# Servo_driver.net
KiCad netlist of a schematic drawn in Altium Designer
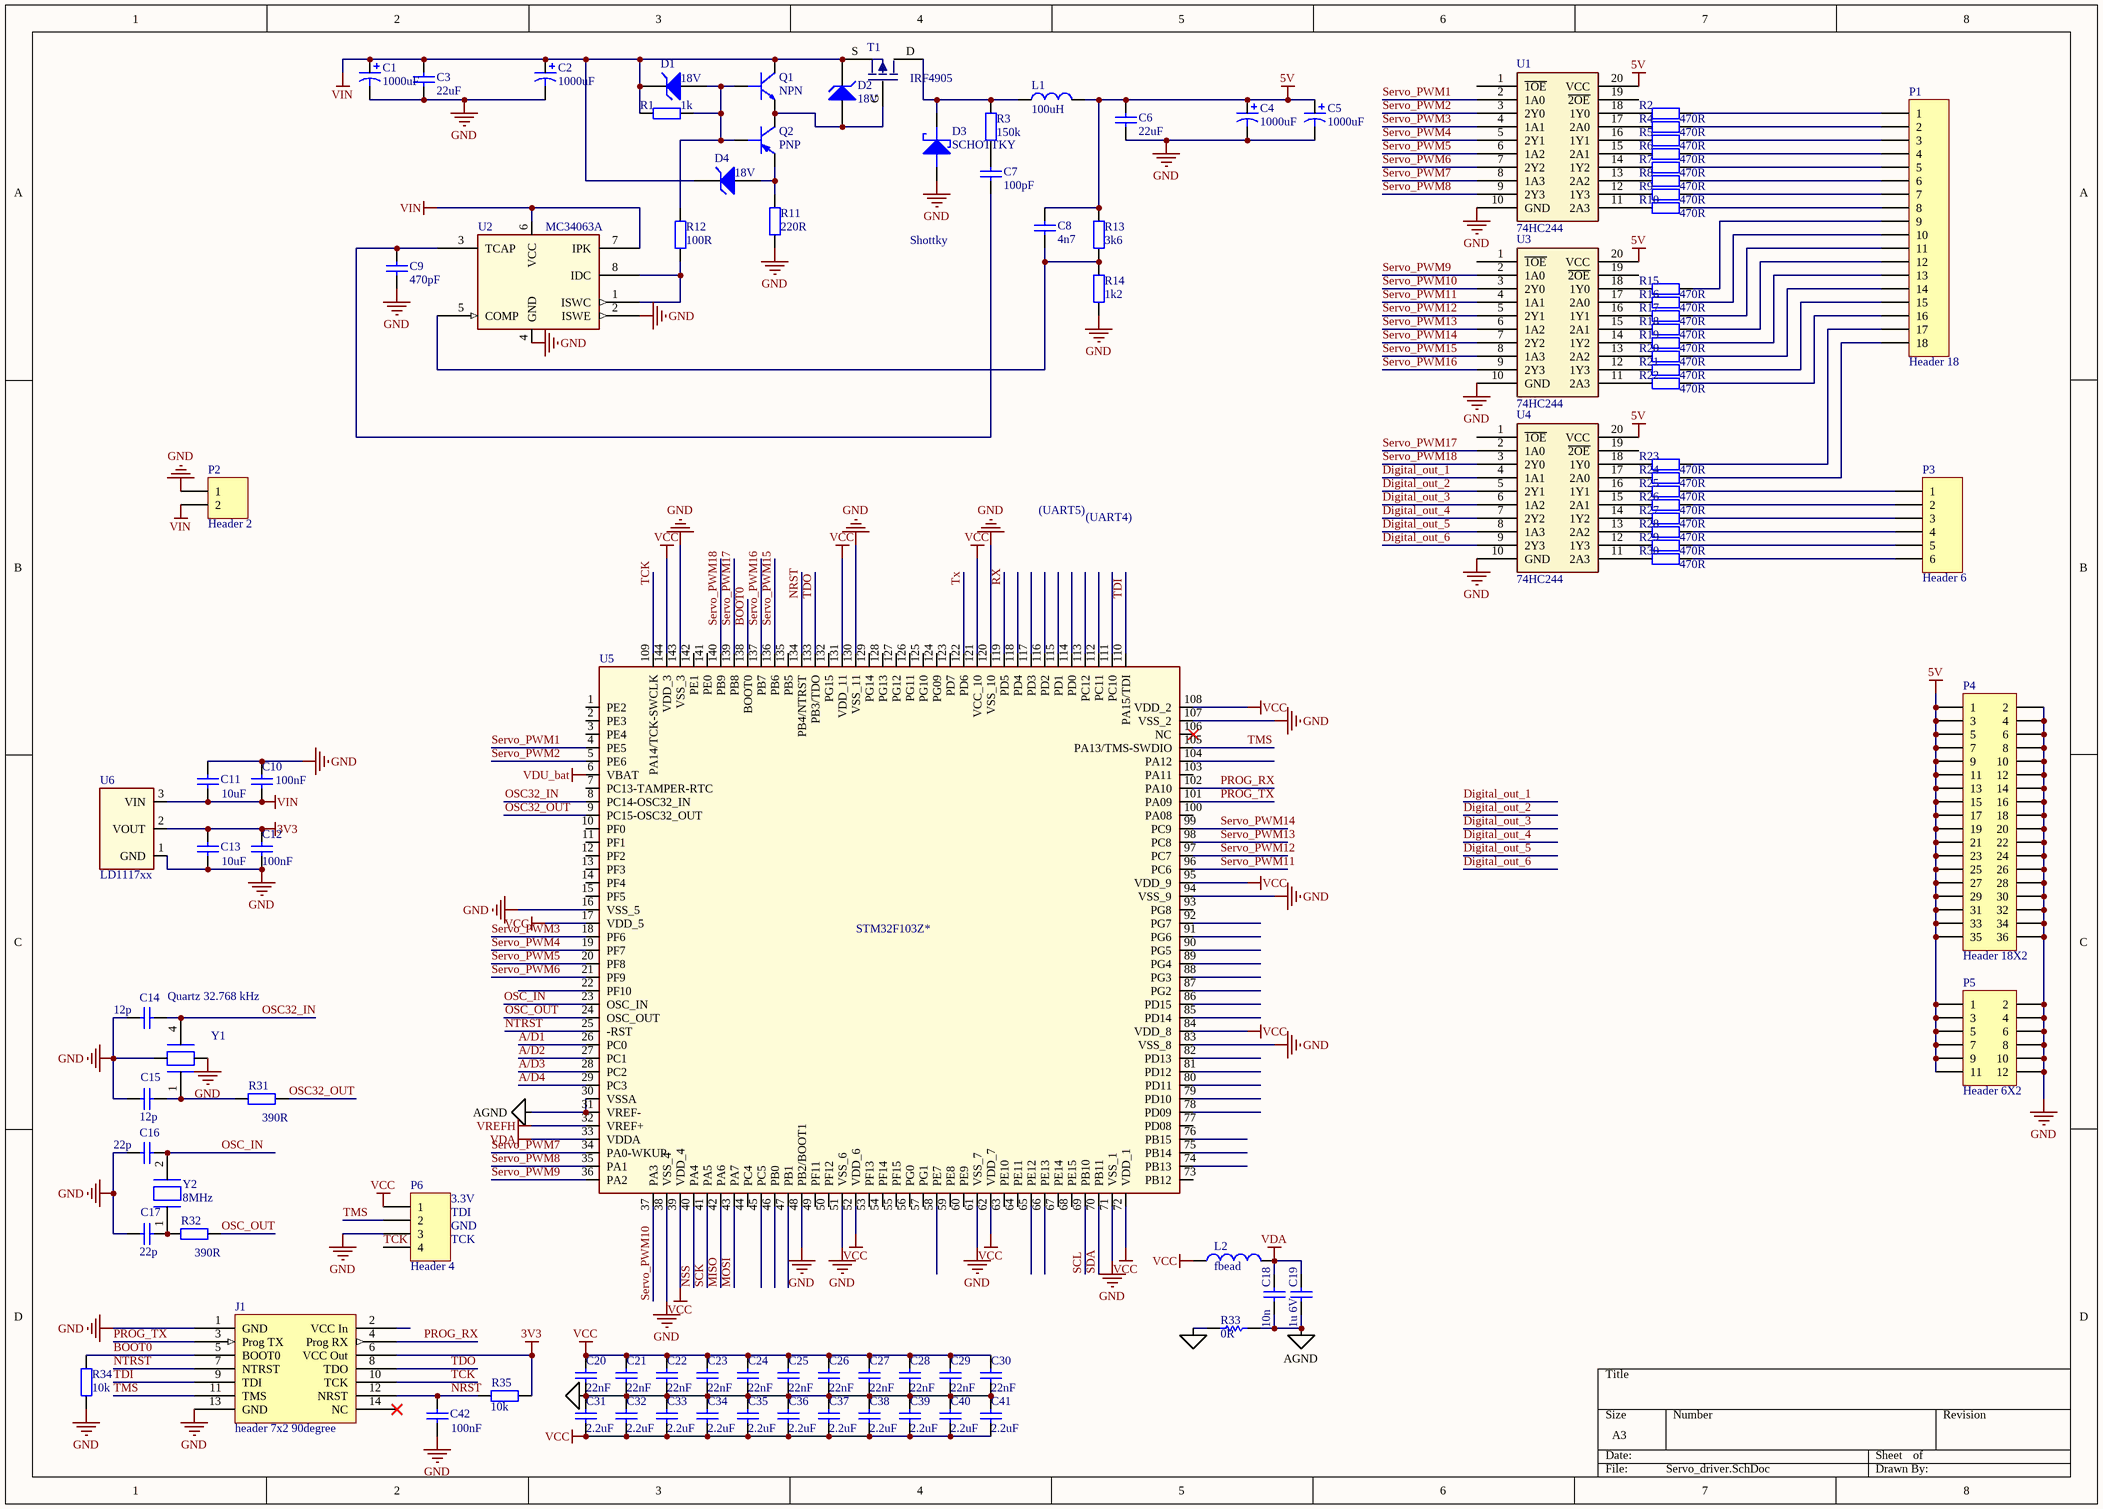
[diagram p0: Servo_driver.SchDoc]

(export (version "E")
  (design (tool "Eeschema 10.0.6"))
  (components
    (comp (ref "C1")
      (value "1000uF")
      (footprint "cap_10x12")
      (description "Polarized Capacitor")
      (libsource (lib "Capacitor") (part "CAP_ELECT"))
    )
    (comp (ref "C2")
      (value "1000uF")
      (footprint "cap_10x12")
      (description "Polarized Capacitor")
      (libsource (lib "Capacitor") (part "CAP_ELECT"))
    )
    (comp (ref "C3")
      (value "22uF")
      (footprint "FP_1210_CAP_N")
      (description "Capacitor")
      (libsource (lib "Capacitor") (part "CAP"))
    )
    (comp (ref "C4")
      (value "1000uF")
      (footprint "cap_10x12")
      (description "Polarized Capacitor")
      (libsource (lib "Capacitor") (part "CAP_ELECT"))
    )
    (comp (ref "C5")
      (value "1000uF")
      (footprint "cap_10x12")
      (description "Polarized Capacitor")
      (libsource (lib "Capacitor") (part "CAP_ELECT"))
    )
    (comp (ref "C6")
      (value "22uF")
      (footprint "FP_1210_CAP_N")
      (description "Capacitor")
      (libsource (lib "Capacitor") (part "CAP"))
    )
    (comp (ref "C7")
      (value "100pF")
      (footprint "FP_0603_CAP_080")
      (description "Capacitor")
      (fields (field (name "PUBLISHER") "Altium Limited"))
      (libsource (lib "Miscellaneous Devices") (part "Cap"))
    )
    (comp (ref "C8")
      (value "4n7")
      (footprint "FP_0603_CAP_080")
      (description "Capacitor")
      (fields (field (name "PUBLISHER") "Altium Limited"))
      (libsource (lib "Miscellaneous Devices") (part "Cap"))
    )
    (comp (ref "C9")
      (value "470pF")
      (footprint "FP_0603_CAP_080")
      (description "Capacitor")
      (fields (field (name "PUBLISHER") "Altium Limited"))
      (libsource (lib "Miscellaneous Devices") (part "Cap"))
    )
    (comp (ref "C10")
      (value "100nF")
      (footprint "FP_0603_CAP_080")
      (description "Capacitor")
      (fields (field (name "PUBLISHER") "Altium Limited"))
      (libsource (lib "Miscellaneous Devices") (part "Cap"))
    )
    (comp (ref "C11")
      (value "10uF")
      (footprint "FP_1206_CAP_085")
      (description "Capacitor")
      (fields (field (name "PUBLISHER") "Altium Limited"))
      (libsource (lib "Miscellaneous Devices") (part "Cap"))
    )
    (comp (ref "C12")
      (value "100nF")
      (footprint "FP_0603_CAP_080")
      (description "Capacitor")
      (fields (field (name "PUBLISHER") "Altium Limited"))
      (libsource (lib "Miscellaneous Devices") (part "Cap"))
    )
    (comp (ref "C13")
      (value "10uF")
      (footprint "FP_1206_CAP_085")
      (description "Capacitor")
      (fields (field (name "PUBLISHER") "Altium Limited"))
      (libsource (lib "Miscellaneous Devices") (part "Cap"))
    )
    (comp (ref "C14")
      (value "12p")
      (footprint "FP_0603_CAP_080")
      (description "Capacitor")
      (fields (field (name "PUBLISHER") "Altium Limited"))
      (libsource (lib "Miscellaneous Devices") (part "Cap"))
    )
    (comp (ref "C15")
      (value "12p")
      (footprint "FP_0603_CAP_080")
      (description "Capacitor")
      (fields (field (name "PUBLISHER") "Altium Limited"))
      (libsource (lib "Miscellaneous Devices") (part "Cap"))
    )
    (comp (ref "C16")
      (value "22p")
      (footprint "FP_0603_CAP_080")
      (description "Capacitor")
      (fields (field (name "PUBLISHER") "Altium Limited"))
      (libsource (lib "Miscellaneous Devices") (part "Cap"))
    )
    (comp (ref "C17")
      (value "22p")
      (footprint "FP_0603_CAP_080")
      (description "Capacitor")
      (fields (field (name "PUBLISHER") "Altium Limited"))
      (libsource (lib "Miscellaneous Devices") (part "Cap"))
    )
    (comp (ref "C18")
      (value "10n")
      (footprint "FP_0603_CAP_080")
      (description "Capacitor")
      (fields (field (name "PUBLISHER") "Altium Limited"))
      (libsource (lib "Miscellaneous Devices") (part "Cap"))
    )
    (comp (ref "C19")
      (value "1u 6V")
      (footprint "FP_0603_CAP_080")
      (description "Capacitor")
      (fields (field (name "PUBLISHER") "Altium Limited"))
      (libsource (lib "Miscellaneous Devices") (part "Cap"))
    )
    (comp (ref "C20")
      (value "22nF")
      (footprint "FP_0603_CAP_080")
      (description "Capacitor")
      (fields (field (name "PUBLISHER") "Altium Limited"))
      (libsource (lib "Miscellaneous Devices") (part "Cap"))
    )
    (comp (ref "C21")
      (value "22nF")
      (footprint "FP_0603_CAP_080")
      (description "Capacitor")
      (fields (field (name "PUBLISHER") "Altium Limited"))
      (libsource (lib "Miscellaneous Devices") (part "Cap"))
    )
    (comp (ref "C22")
      (value "22nF")
      (footprint "FP_0603_CAP_080")
      (description "Capacitor")
      (fields (field (name "PUBLISHER") "Altium Limited"))
      (libsource (lib "Miscellaneous Devices") (part "Cap"))
    )
    (comp (ref "C23")
      (value "22nF")
      (footprint "FP_0603_CAP_080")
      (description "Capacitor")
      (fields (field (name "PUBLISHER") "Altium Limited"))
      (libsource (lib "Miscellaneous Devices") (part "Cap"))
    )
    (comp (ref "C24")
      (value "22nF")
      (footprint "FP_0603_CAP_080")
      (description "Capacitor")
      (fields (field (name "PUBLISHER") "Altium Limited"))
      (libsource (lib "Miscellaneous Devices") (part "Cap"))
    )
    (comp (ref "C25")
      (value "22nF")
      (footprint "FP_0603_CAP_080")
      (description "Capacitor")
      (fields (field (name "PUBLISHER") "Altium Limited"))
      (libsource (lib "Miscellaneous Devices") (part "Cap"))
    )
    (comp (ref "C26")
      (value "22nF")
      (footprint "FP_0603_CAP_080")
      (description "Capacitor")
      (fields (field (name "PUBLISHER") "Altium Limited"))
      (libsource (lib "Miscellaneous Devices") (part "Cap"))
    )
    (comp (ref "C27")
      (value "22nF")
      (footprint "FP_0603_CAP_080")
      (description "Capacitor")
      (fields (field (name "PUBLISHER") "Altium Limited"))
      (libsource (lib "Miscellaneous Devices") (part "Cap"))
    )
    (comp (ref "C28")
      (value "22nF")
      (footprint "FP_0603_CAP_080")
      (description "Capacitor")
      (fields (field (name "PUBLISHER") "Altium Limited"))
      (libsource (lib "Miscellaneous Devices") (part "Cap"))
    )
    (comp (ref "C29")
      (value "22nF")
      (footprint "FP_0603_CAP_080")
      (description "Capacitor")
      (fields (field (name "PUBLISHER") "Altium Limited"))
      (libsource (lib "Miscellaneous Devices") (part "Cap"))
    )
    (comp (ref "C30")
      (value "22nF")
      (footprint "FP_0603_CAP_080")
      (description "Capacitor")
      (fields (field (name "PUBLISHER") "Altium Limited"))
      (libsource (lib "Miscellaneous Devices") (part "Cap"))
    )
    (comp (ref "C31")
      (value "2.2uF")
      (footprint "FP_0603_CAP_080")
      (description "Capacitor")
      (fields (field (name "PUBLISHER") "Altium Limited"))
      (libsource (lib "Miscellaneous Devices") (part "Cap"))
    )
    (comp (ref "C32")
      (value "2.2uF")
      (footprint "FP_0603_CAP_080")
      (description "Capacitor")
      (fields (field (name "PUBLISHER") "Altium Limited"))
      (libsource (lib "Miscellaneous Devices") (part "Cap"))
    )
    (comp (ref "C33")
      (value "2.2uF")
      (footprint "FP_0603_CAP_080")
      (description "Capacitor")
      (fields (field (name "PUBLISHER") "Altium Limited"))
      (libsource (lib "Miscellaneous Devices") (part "Cap"))
    )
    (comp (ref "C34")
      (value "2.2uF")
      (footprint "FP_0603_CAP_080")
      (description "Capacitor")
      (fields (field (name "PUBLISHER") "Altium Limited"))
      (libsource (lib "Miscellaneous Devices") (part "Cap"))
    )
    (comp (ref "C35")
      (value "2.2uF")
      (footprint "FP_0603_CAP_080")
      (description "Capacitor")
      (fields (field (name "PUBLISHER") "Altium Limited"))
      (libsource (lib "Miscellaneous Devices") (part "Cap"))
    )
    (comp (ref "C36")
      (value "2.2uF")
      (footprint "FP_0603_CAP_080")
      (description "Capacitor")
      (fields (field (name "PUBLISHER") "Altium Limited"))
      (libsource (lib "Miscellaneous Devices") (part "Cap"))
    )
    (comp (ref "C37")
      (value "2.2uF")
      (footprint "FP_0603_CAP_080")
      (description "Capacitor")
      (fields (field (name "PUBLISHER") "Altium Limited"))
      (libsource (lib "Miscellaneous Devices") (part "Cap"))
    )
    (comp (ref "C38")
      (value "2.2uF")
      (footprint "FP_0603_CAP_080")
      (description "Capacitor")
      (fields (field (name "PUBLISHER") "Altium Limited"))
      (libsource (lib "Miscellaneous Devices") (part "Cap"))
    )
    (comp (ref "C39")
      (value "2.2uF")
      (footprint "FP_0603_CAP_080")
      (description "Capacitor")
      (fields (field (name "PUBLISHER") "Altium Limited"))
      (libsource (lib "Miscellaneous Devices") (part "Cap"))
    )
    (comp (ref "C40")
      (value "2.2uF")
      (footprint "FP_0603_CAP_080")
      (description "Capacitor")
      (fields (field (name "PUBLISHER") "Altium Limited"))
      (libsource (lib "Miscellaneous Devices") (part "Cap"))
    )
    (comp (ref "C41")
      (value "2.2uF")
      (footprint "FP_0603_CAP_080")
      (description "Capacitor")
      (fields (field (name "PUBLISHER") "Altium Limited"))
      (libsource (lib "Miscellaneous Devices") (part "Cap"))
    )
    (comp (ref "C42")
      (value "100nF")
      (footprint "FP_0603_CAP_080")
      (description "Capacitor")
      (fields (field (name "PUBLISHER") "Altium Limited"))
      (libsource (lib "Miscellaneous Devices") (part "Cap"))
    )
    (comp (ref "D1")
      (value "18V")
      (footprint "SOD-80")
      (description "Zener Diode")
      (libsource (lib "Diode") (part "ZENER"))
    )
    (comp (ref "D2")
      (value "18V")
      (footprint "SOD-80")
      (description "Zener Diode")
      (libsource (lib "Diode") (part "ZENER"))
    )
    (comp (ref "D3")
      (value "SCHOTTKY")
      (footprint "DIODE_TO220")
      (description "NXP - PMEG3020EJ,115 - SCHOTTKY RECT 30V 2A SOD323F")
      (libsource (lib "Diode") (part "SCHOTTKY"))
    )
    (comp (ref "D4")
      (value "18V")
      (footprint "SOD-80")
      (description "Zener Diode")
      (libsource (lib "Diode") (part "ZENER"))
    )
    (comp (ref "J1")
      (value "header 7x2 90degree")
      (footprint "SMD_header_2x7_narrow")
      (libsource (lib "Fufi_altium_lib") (part "ARM_JTAG_PROG"))
    )
    (comp (ref "L1") (value "100uH") (footprint "SRR1206_T") (libsource (lib "Inductor") (part "L")))
    (comp (ref "L2")
      (value "fbead")
      (footprint "FP_0805_RES_SIMPLE")
      (description "FBEAD")
      (fields (field (name "PUBLISHER") "Altium Limited"))
      (libsource (lib "Miscellaneous Devices") (part "Inductor"))
    )
    (comp (ref "P1")
      (value "Header 18")
      (footprint "HDR1X18")
      (description "Header, 18-Pin")
      (fields (field (name "PUBLISHER") "Altium Limited"))
      (libsource (lib "Miscellaneous Connectors") (part "Header 18"))
    )
    (comp (ref "P2")
      (value "Header 2")
      (footprint "Sorkapocs 2P 5mm")
      (description "Header, 2-Pin")
      (fields (field (name "PUBLISHER") "Altium Limited"))
      (libsource (lib "Miscellaneous Connectors") (part "Header 2"))
    )
    (comp (ref "P3")
      (value "Header 6")
      (footprint "HDR1X6")
      (description "Header, 6-Pin")
      (fields (field (name "PUBLISHER") "Altium Limited"))
      (libsource (lib "Miscellaneous Connectors") (part "Header 6"))
    )
    (comp (ref "P4")
      (value "Header 18X2")
      (footprint "HDR2X18")
      (description "Header, 18-Pin, Dual row")
      (fields (field (name "PUBLISHER") "Altium Limited"))
      (libsource (lib "Miscellaneous Connectors") (part "Header 18X2"))
    )
    (comp (ref "P5")
      (value "Header 6X2")
      (footprint "HDR2X6")
      (description "Header, 6-Pin, Dual row")
      (fields (field (name "PUBLISHER") "Altium Limited"))
      (libsource (lib "Miscellaneous Connectors") (part "Header 6X2"))
    )
    (comp (ref "P6")
      (value "Header 4")
      (footprint "HDR1X4")
      (description "Header, 4-Pin")
      (fields (field (name "PUBLISHER") "Altium Limited"))
      (libsource (lib "Miscellaneous Connectors") (part "Header 4"))
    )
    (comp (ref "Q1") (value "NPN") (footprint "TR_SOT23") (libsource (lib "Transistor") (part "NPN")))
    (comp (ref "Q2") (value "PNP") (footprint "TR_SOT23") (libsource (lib "Transistor") (part "PNP")))
    (comp (ref "R1")
      (value "1k")
      (footprint "FP_1206_RES")
      (description "Resistor")
      (fields (field (name "PUBLISHER") "Altium Limited"))
      (libsource (lib "") (part "Res3_1"))
    )
    (comp (ref "R2")
      (value "470R")
      (footprint "FP_0603_RES")
      (description "Resistor")
      (fields (field (name "PUBLISHER") "Altium Limited"))
      (libsource (lib "Miscellaneous Devices") (part "Res3"))
    )
    (comp (ref "R3")
      (value "150k")
      (footprint "FP_0603_RES")
      (description "Resistor")
      (fields (field (name "PUBLISHER") "Altium Limited"))
      (libsource (lib "") (part "Res3_3"))
    )
    (comp (ref "R4")
      (value "470R")
      (footprint "FP_0603_RES")
      (description "Resistor")
      (fields (field (name "PUBLISHER") "Altium Limited"))
      (libsource (lib "Miscellaneous Devices") (part "Res3"))
    )
    (comp (ref "R5")
      (value "470R")
      (footprint "FP_0603_RES")
      (description "Resistor")
      (fields (field (name "PUBLISHER") "Altium Limited"))
      (libsource (lib "Miscellaneous Devices") (part "Res3"))
    )
    (comp (ref "R6")
      (value "470R")
      (footprint "FP_0603_RES")
      (description "Resistor")
      (fields (field (name "PUBLISHER") "Altium Limited"))
      (libsource (lib "Miscellaneous Devices") (part "Res3"))
    )
    (comp (ref "R7")
      (value "470R")
      (footprint "FP_0603_RES")
      (description "Resistor")
      (fields (field (name "PUBLISHER") "Altium Limited"))
      (libsource (lib "Miscellaneous Devices") (part "Res3"))
    )
    (comp (ref "R8")
      (value "470R")
      (footprint "FP_0603_RES")
      (description "Resistor")
      (fields (field (name "PUBLISHER") "Altium Limited"))
      (libsource (lib "Miscellaneous Devices") (part "Res3"))
    )
    (comp (ref "R9")
      (value "470R")
      (footprint "FP_0603_RES")
      (description "Resistor")
      (fields (field (name "PUBLISHER") "Altium Limited"))
      (libsource (lib "Miscellaneous Devices") (part "Res3"))
    )
    (comp (ref "R10")
      (value "470R")
      (footprint "FP_0603_RES")
      (description "Resistor")
      (fields (field (name "PUBLISHER") "Altium Limited"))
      (libsource (lib "Miscellaneous Devices") (part "Res3"))
    )
    (comp (ref "R11")
      (value "220R")
      (footprint "FP_1206_RES")
      (description "Resistor")
      (fields (field (name "PUBLISHER") "Altium Limited"))
      (libsource (lib "") (part "Res3_2"))
    )
    (comp (ref "R12")
      (value "100R")
      (footprint "FP_1206_RES")
      (description "Resistor")
      (fields (field (name "PUBLISHER") "Altium Limited"))
      (libsource (lib "") (part "Res3_2"))
    )
    (comp (ref "R13")
      (value "3k6")
      (footprint "FP_0603_RES")
      (description "Resistor")
      (fields (field (name "PUBLISHER") "Altium Limited"))
      (libsource (lib "") (part "Res3_2"))
    )
    (comp (ref "R14")
      (value "1k2")
      (footprint "FP_0603_RES")
      (description "Resistor")
      (fields (field (name "PUBLISHER") "Altium Limited"))
      (libsource (lib "") (part "Res3_2"))
    )
    (comp (ref "R15")
      (value "470R")
      (footprint "FP_0603_RES")
      (description "Resistor")
      (fields (field (name "PUBLISHER") "Altium Limited"))
      (libsource (lib "Miscellaneous Devices") (part "Res3"))
    )
    (comp (ref "R16")
      (value "470R")
      (footprint "FP_0603_RES")
      (description "Resistor")
      (fields (field (name "PUBLISHER") "Altium Limited"))
      (libsource (lib "Miscellaneous Devices") (part "Res3"))
    )
    (comp (ref "R17")
      (value "470R")
      (footprint "FP_0603_RES")
      (description "Resistor")
      (fields (field (name "PUBLISHER") "Altium Limited"))
      (libsource (lib "Miscellaneous Devices") (part "Res3"))
    )
    (comp (ref "R18")
      (value "470R")
      (footprint "FP_0603_RES")
      (description "Resistor")
      (fields (field (name "PUBLISHER") "Altium Limited"))
      (libsource (lib "Miscellaneous Devices") (part "Res3"))
    )
    (comp (ref "R19")
      (value "470R")
      (footprint "FP_0603_RES")
      (description "Resistor")
      (fields (field (name "PUBLISHER") "Altium Limited"))
      (libsource (lib "Miscellaneous Devices") (part "Res3"))
    )
    (comp (ref "R20")
      (value "470R")
      (footprint "FP_0603_RES")
      (description "Resistor")
      (fields (field (name "PUBLISHER") "Altium Limited"))
      (libsource (lib "Miscellaneous Devices") (part "Res3"))
    )
    (comp (ref "R21")
      (value "470R")
      (footprint "FP_0603_RES")
      (description "Resistor")
      (fields (field (name "PUBLISHER") "Altium Limited"))
      (libsource (lib "Miscellaneous Devices") (part "Res3"))
    )
    (comp (ref "R22")
      (value "470R")
      (footprint "FP_0603_RES")
      (description "Resistor")
      (fields (field (name "PUBLISHER") "Altium Limited"))
      (libsource (lib "Miscellaneous Devices") (part "Res3"))
    )
    (comp (ref "R23")
      (value "470R")
      (footprint "FP_0603_RES")
      (description "Resistor")
      (fields (field (name "PUBLISHER") "Altium Limited"))
      (libsource (lib "Miscellaneous Devices") (part "Res3"))
    )
    (comp (ref "R24")
      (value "470R")
      (footprint "FP_0603_RES")
      (description "Resistor")
      (fields (field (name "PUBLISHER") "Altium Limited"))
      (libsource (lib "Miscellaneous Devices") (part "Res3"))
    )
    (comp (ref "R25")
      (value "470R")
      (footprint "FP_0603_RES")
      (description "Resistor")
      (fields (field (name "PUBLISHER") "Altium Limited"))
      (libsource (lib "Miscellaneous Devices") (part "Res3"))
    )
    (comp (ref "R26")
      (value "470R")
      (footprint "FP_0603_RES")
      (description "Resistor")
      (fields (field (name "PUBLISHER") "Altium Limited"))
      (libsource (lib "Miscellaneous Devices") (part "Res3"))
    )
    (comp (ref "R27")
      (value "470R")
      (footprint "FP_0603_RES")
      (description "Resistor")
      (fields (field (name "PUBLISHER") "Altium Limited"))
      (libsource (lib "Miscellaneous Devices") (part "Res3"))
    )
    (comp (ref "R28")
      (value "470R")
      (footprint "FP_0603_RES")
      (description "Resistor")
      (fields (field (name "PUBLISHER") "Altium Limited"))
      (libsource (lib "Miscellaneous Devices") (part "Res3"))
    )
    (comp (ref "R29")
      (value "470R")
      (footprint "FP_0603_RES")
      (description "Resistor")
      (fields (field (name "PUBLISHER") "Altium Limited"))
      (libsource (lib "Miscellaneous Devices") (part "Res3"))
    )
    (comp (ref "R30")
      (value "470R")
      (footprint "FP_0603_RES")
      (description "Resistor")
      (fields (field (name "PUBLISHER") "Altium Limited"))
      (libsource (lib "Miscellaneous Devices") (part "Res3"))
    )
    (comp (ref "R31")
      (value "390R")
      (footprint "FP_0603_RES")
      (description "Resistor")
      (fields (field (name "PUBLISHER") "Altium Limited"))
      (libsource (lib "") (part "Res3_1"))
    )
    (comp (ref "R32")
      (value "390R")
      (footprint "FP_0603_RES")
      (description "Resistor")
      (fields (field (name "PUBLISHER") "Altium Limited"))
      (libsource (lib "") (part "Res3_1"))
    )
    (comp (ref "R33")
      (value "0R")
      (footprint "FP_0603_RES")
      (description "Resistor")
      (fields (field (name "PUBLISHER") "Altium Limited"))
      (libsource (lib "Miscellaneous Devices") (part "Res1"))
    )
    (comp (ref "R34")
      (value "10k")
      (footprint "FP_0603_RES")
      (description "Resistor")
      (fields (field (name "PUBLISHER") "Altium Limited"))
      (libsource (lib "") (part "Res3_3"))
    )
    (comp (ref "R35")
      (value "10k")
      (footprint "FP_0603_RES")
      (description "Resistor")
      (fields (field (name "PUBLISHER") "Altium Limited"))
      (libsource (lib "Miscellaneous Devices") (part "Res3"))
    )
    (comp (ref "T1") (value "IRF4905") (footprint "FET_TO220") (libsource (lib "FET") (part "PMOS")))
    (comp (ref "U1")
      (value "74HC244")
      (footprint "DIGITAL_SOIC20W")
      (description "Octqal buffer 3-state line driver")
      (libsource (lib "Digital") (part "74HC244"))
    )
    (comp (ref "U2")
      (value "MC34063A")
      (footprint "FP_SO8_MS012AA")
      (libsource (lib "Supply") (part "MC34063A"))
    )
    (comp (ref "U3")
      (value "74HC244")
      (footprint "DIGITAL_SOIC20W")
      (description "Octqal buffer 3-state line driver")
      (libsource (lib "Digital") (part "74HC244"))
    )
    (comp (ref "U4")
      (value "74HC244")
      (footprint "DIGITAL_SOIC20W")
      (description "Octqal buffer 3-state line driver")
      (libsource (lib "Digital") (part "74HC244"))
    )
    (comp (ref "U5")
      (value "STM32F103Z*")
      (footprint "LQFP144")
      (libsource (lib "FUFI_Library") (part "STM32F103Zxxx"))
    )
    (comp (ref "U6")
      (value "LD1117xx")
      (footprint "SUPPLY_SOT223")
      (description "LD1117xx 3,3V lin reg")
      (libsource (lib "Supply") (part "LD1117xx"))
    )
    (comp (ref "Y1")
      (value "Quartz 32.768 kHz")
      (footprint "XTAL_ABS25")
      (description "XTAL_32,768khz ABS25 SMD")
      (libsource (lib "Qartz") (part "XTAL_32,768khz ABS25 SMD"))
    )
    (comp (ref "Y2")
      (value "8MHz")
      (footprint "FP_CRYSTAL_HC49_SMD")
      (description "Standard HC49 quartz")
      (fields (field (name "MANUFACTURER") "Siward") (field (name "Comment") "8MHz Quartz HC49"))
      (libsource (lib "Fufi_altium_lib") (part "XTAL HC49"))
    )
  )
  (nets
    (net (code "1") (name "/A{slash}D1") (class "Default")
      (node (ref "U5") (pin "26") (pinfunction "PC0_26") (pintype "passive"))
    )
    (net (code "2") (name "/A{slash}D2") (class "Default")
      (node (ref "U5") (pin "27") (pinfunction "PC1_27") (pintype "passive"))
    )
    (net (code "3") (name "/A{slash}D3") (class "Default")
      (node (ref "U5") (pin "28") (pinfunction "PC2_28") (pintype "passive"))
    )
    (net (code "4") (name "/A{slash}D4") (class "Default")
      (node (ref "U5") (pin "29") (pinfunction "PC3_29") (pintype "passive"))
    )
    (net (code "5") (name "/BOOT0") (class "Default")
      (node (ref "J1") (pin "5") (pinfunction "BOOT0_5") (pintype "passive"))
      (node (ref "R34") (pin "1") (pinfunction "1_1") (pintype "passive"))
      (node (ref "U5") (pin "138") (pinfunction "BOOT0_138") (pintype "passive"))
    )
    (net (code "6") (name "/Digital_out_1") (class "Default")
      (node (ref "U4") (pin "4") (pinfunction "1A1_4") (pintype "passive"))
    )
    (net (code "7") (name "/Digital_out_2") (class "Default")
      (node (ref "U4") (pin "5") (pinfunction "2Y1_5") (pintype "passive"))
    )
    (net (code "8") (name "/Digital_out_3") (class "Default")
      (node (ref "U4") (pin "6") (pinfunction "1A2_6") (pintype "passive"))
    )
    (net (code "9") (name "/Digital_out_4") (class "Default")
      (node (ref "U4") (pin "7") (pinfunction "2Y2_7") (pintype "passive"))
    )
    (net (code "10") (name "/Digital_out_5") (class "Default")
      (node (ref "U4") (pin "8") (pinfunction "1A3_8") (pintype "passive"))
    )
    (net (code "11") (name "/Digital_out_6") (class "Default")
      (node (ref "U4") (pin "9") (pinfunction "2Y3_9") (pintype "passive"))
    )
    (net (code "12") (name "/MISO") (class "Default")
      (node (ref "U5") (pin "42") (pinfunction "PA6_42") (pintype "passive"))
    )
    (net (code "13") (name "/MOSI") (class "Default")
      (node (ref "U5") (pin "43") (pinfunction "PA7_43") (pintype "passive"))
    )
    (net (code "14") (name "/NRST") (class "Default")
      (node (ref "C42") (pin "1") (pinfunction "1_1") (pintype "passive"))
      (node (ref "J1") (pin "12") (pinfunction "NRST_12") (pintype "passive"))
      (node (ref "R35") (pin "1") (pinfunction "1_1") (pintype "passive"))
      (node (ref "U5") (pin "134") (pinfunction "PB4/NTRST_134") (pintype "passive"))
    )
    (net (code "15") (name "/NSS") (class "Default")
      (node (ref "U5") (pin "40") (pinfunction "PA4_40") (pintype "passive"))
    )
    (net (code "16") (name "/NTRST") (class "Default")
      (node (ref "J1") (pin "7") (pinfunction "NTRST_7") (pintype "passive"))
      (node (ref "U5") (pin "25") (pinfunction "-RST_25") (pintype "passive"))
    )
    (net (code "17") (name "/OSC32_IN") (class "Default")
      (node (ref "C14") (pin "2") (pinfunction "2_2") (pintype "passive"))
      (node (ref "U5") (pin "8") (pinfunction "PC14-OSC32_IN_8") (pintype "passive"))
      (node (ref "Y1") (pin "4") (pinfunction "4_4") (pintype "passive"))
    )
    (net (code "18") (name "/OSC32_OUT") (class "Default")
      (node (ref "R31") (pin "1") (pinfunction "1_1") (pintype "passive"))
      (node (ref "U5") (pin "9") (pinfunction "PC15-OSC32_OUT_9") (pintype "passive"))
    )
    (net (code "19") (name "/OSC_IN") (class "Default")
      (node (ref "C16") (pin "2") (pinfunction "2_2") (pintype "passive"))
      (node (ref "U5") (pin "23") (pinfunction "OSC_IN_23") (pintype "passive"))
      (node (ref "Y2") (pin "2") (pinfunction "2_2") (pintype "passive"))
    )
    (net (code "20") (name "/OSC_OUT") (class "Default")
      (node (ref "R32") (pin "1") (pinfunction "1_1") (pintype "passive"))
      (node (ref "U5") (pin "24") (pinfunction "OSC_OUT_24") (pintype "passive"))
    )
    (net (code "21") (name "/PROG_RX") (class "Default")
      (node (ref "J1") (pin "4") (pinfunction "Prog_RX_4") (pintype "output"))
      (node (ref "U5") (pin "102") (pinfunction "PA10_102") (pintype "passive"))
    )
    (net (code "22") (name "/PROG_TX") (class "Default")
      (node (ref "J1") (pin "3") (pinfunction "Prog_TX_3") (pintype "input"))
      (node (ref "U5") (pin "101") (pinfunction "PA09_101") (pintype "passive"))
    )
    (net (code "23") (name "/RX") (class "Default")
      (node (ref "U5") (pin "119") (pinfunction "PD5_119") (pintype "passive"))
    )
    (net (code "24") (name "/SCK") (class "Default")
      (node (ref "U5") (pin "41") (pinfunction "PA5_41") (pintype "passive"))
    )
    (net (code "25") (name "/SCL") (class "Default")
      (node (ref "U5") (pin "69") (pinfunction "PB10_69") (pintype "passive"))
    )
    (net (code "26") (name "/SDA") (class "Default")
      (node (ref "U5") (pin "70") (pinfunction "PB11_70") (pintype "passive"))
    )
    (net (code "27") (name "/Servo_PWM1") (class "Default")
      (node (ref "U1") (pin "2") (pinfunction "1A0_2") (pintype "passive"))
      (node (ref "U5") (pin "4") (pinfunction "PE5_4") (pintype "passive"))
    )
    (net (code "28") (name "/Servo_PWM2") (class "Default")
      (node (ref "U1") (pin "3") (pinfunction "2Y0_3") (pintype "passive"))
      (node (ref "U5") (pin "5") (pinfunction "PE6_5") (pintype "passive"))
    )
    (net (code "29") (name "/Servo_PWM3") (class "Default")
      (node (ref "U1") (pin "4") (pinfunction "1A1_4") (pintype "passive"))
      (node (ref "U5") (pin "18") (pinfunction "PF6_18") (pintype "passive"))
    )
    (net (code "30") (name "/Servo_PWM4") (class "Default")
      (node (ref "U1") (pin "5") (pinfunction "2Y1_5") (pintype "passive"))
      (node (ref "U5") (pin "19") (pinfunction "PF7_19") (pintype "passive"))
    )
    (net (code "31") (name "/Servo_PWM5") (class "Default")
      (node (ref "U1") (pin "6") (pinfunction "1A2_6") (pintype "passive"))
      (node (ref "U5") (pin "20") (pinfunction "PF8_20") (pintype "passive"))
    )
    (net (code "32") (name "/Servo_PWM6") (class "Default")
      (node (ref "U1") (pin "7") (pinfunction "2Y2_7") (pintype "passive"))
      (node (ref "U5") (pin "21") (pinfunction "PF9_21") (pintype "passive"))
    )
    (net (code "33") (name "/Servo_PWM7") (class "Default")
      (node (ref "U1") (pin "8") (pinfunction "1A3_8") (pintype "passive"))
      (node (ref "U5") (pin "34") (pinfunction "PA0-WKUP_34") (pintype "passive"))
    )
    (net (code "34") (name "/Servo_PWM8") (class "Default")
      (node (ref "U1") (pin "9") (pinfunction "2Y3_9") (pintype "passive"))
      (node (ref "U5") (pin "35") (pinfunction "PA1_35") (pintype "passive"))
    )
    (net (code "35") (name "/Servo_PWM9") (class "Default")
      (node (ref "U3") (pin "2") (pinfunction "1A0_2") (pintype "passive"))
      (node (ref "U5") (pin "36") (pinfunction "PA2_36") (pintype "passive"))
    )
    (net (code "36") (name "/Servo_PWM10") (class "Default")
      (node (ref "U3") (pin "3") (pinfunction "2Y0_3") (pintype "passive"))
      (node (ref "U5") (pin "37") (pinfunction "PA3_37") (pintype "passive"))
    )
    (net (code "37") (name "/Servo_PWM11") (class "Default")
      (node (ref "U3") (pin "4") (pinfunction "1A1_4") (pintype "passive"))
      (node (ref "U5") (pin "96") (pinfunction "PC6_96") (pintype "passive"))
    )
    (net (code "38") (name "/Servo_PWM12") (class "Default")
      (node (ref "U3") (pin "5") (pinfunction "2Y1_5") (pintype "passive"))
      (node (ref "U5") (pin "97") (pinfunction "PC7_97") (pintype "passive"))
    )
    (net (code "39") (name "/Servo_PWM13") (class "Default")
      (node (ref "U3") (pin "6") (pinfunction "1A2_6") (pintype "passive"))
      (node (ref "U5") (pin "98") (pinfunction "PC8_98") (pintype "passive"))
    )
    (net (code "40") (name "/Servo_PWM14") (class "Default")
      (node (ref "U3") (pin "7") (pinfunction "2Y2_7") (pintype "passive"))
      (node (ref "U5") (pin "99") (pinfunction "PC9_99") (pintype "passive"))
    )
    (net (code "41") (name "/Servo_PWM15") (class "Default")
      (node (ref "U3") (pin "8") (pinfunction "1A3_8") (pintype "passive"))
      (node (ref "U5") (pin "136") (pinfunction "PB6_136") (pintype "passive"))
    )
    (net (code "42") (name "/Servo_PWM16") (class "Default")
      (node (ref "U3") (pin "9") (pinfunction "2Y3_9") (pintype "passive"))
      (node (ref "U5") (pin "137") (pinfunction "PB7_137") (pintype "passive"))
    )
    (net (code "43") (name "/Servo_PWM17") (class "Default")
      (node (ref "U4") (pin "2") (pinfunction "1A0_2") (pintype "passive"))
      (node (ref "U5") (pin "139") (pinfunction "PB8_139") (pintype "passive"))
    )
    (net (code "44") (name "/Servo_PWM18") (class "Default")
      (node (ref "U4") (pin "3") (pinfunction "2Y0_3") (pintype "passive"))
      (node (ref "U5") (pin "140") (pinfunction "PB9_140") (pintype "passive"))
    )
    (net (code "45") (name "/TCK") (class "Default")
      (node (ref "J1") (pin "10") (pinfunction "TCK_10") (pintype "passive"))
      (node (ref "P6") (pin "4") (pinfunction "4_4") (pintype "passive"))
      (node (ref "U5") (pin "109") (pinfunction "PA14/TCK-SWCLK_109") (pintype "passive"))
    )
    (net (code "46") (name "/TDI") (class "Default")
      (node (ref "J1") (pin "9") (pinfunction "TDI_9") (pintype "passive"))
      (node (ref "U5") (pin "110") (pinfunction "PA15/TDI_110") (pintype "passive"))
    )
    (net (code "47") (name "/TDO") (class "Default")
      (node (ref "J1") (pin "8") (pinfunction "TDO_8") (pintype "passive"))
      (node (ref "U5") (pin "133") (pinfunction "PB3/TDO_133") (pintype "passive"))
    )
    (net (code "48") (name "/TMS") (class "Default")
      (node (ref "J1") (pin "11") (pinfunction "TMS_11") (pintype "passive"))
      (node (ref "P6") (pin "2") (pinfunction "2_2") (pintype "passive"))
      (node (ref "U5") (pin "105") (pinfunction "PA13/TMS-SWDIO_105") (pintype "passive"))
    )
    (net (code "49") (name "/Tx") (class "Default")
      (node (ref "U5") (pin "122") (pinfunction "PD6_122") (pintype "passive"))
    )
    (net (code "50") (name "3V3") (class "Default")
      (node (ref "C12") (pin "1") (pinfunction "1_1") (pintype "passive"))
      (node (ref "C13") (pin "2") (pinfunction "2_2") (pintype "passive"))
      (node (ref "J1") (pin "6") (pinfunction "VCC_Out_6") (pintype "passive"))
      (node (ref "R35") (pin "2") (pinfunction "2_2") (pintype "passive"))
      (node (ref "U6") (pin "2") (pinfunction "VOUT_2") (pintype "passive"))
    )
    (net (code "51") (name "5V") (class "Default")
      (node (ref "C4") (pin "P") (pintype "passive"))
      (node (ref "C5") (pin "P") (pintype "passive"))
      (node (ref "C6") (pin "2") (pinfunction "2_2") (pintype "passive"))
      (node (ref "C8") (pin "2") (pinfunction "2_2") (pintype "passive"))
      (node (ref "L1") (pin "2") (pinfunction "2_2") (pintype "passive"))
      (node (ref "P4") (pin "1") (pinfunction "1_1") (pintype "passive"))
      (node (ref "P4") (pin "11") (pinfunction "11_11") (pintype "passive"))
      (node (ref "P4") (pin "13") (pinfunction "13_13") (pintype "passive"))
      (node (ref "P4") (pin "15") (pinfunction "15_15") (pintype "passive"))
      (node (ref "P4") (pin "17") (pinfunction "17_17") (pintype "passive"))
      (node (ref "P4") (pin "19") (pinfunction "19_19") (pintype "passive"))
      (node (ref "P4") (pin "21") (pinfunction "21_21") (pintype "passive"))
      (node (ref "P4") (pin "23") (pinfunction "23_23") (pintype "passive"))
      (node (ref "P4") (pin "25") (pinfunction "25_25") (pintype "passive"))
      (node (ref "P4") (pin "27") (pinfunction "27_27") (pintype "passive"))
      (node (ref "P4") (pin "29") (pinfunction "29_29") (pintype "passive"))
      (node (ref "P4") (pin "3") (pinfunction "3_3") (pintype "passive"))
      (node (ref "P4") (pin "31") (pinfunction "31_31") (pintype "passive"))
      (node (ref "P4") (pin "33") (pinfunction "33_33") (pintype "passive"))
      (node (ref "P4") (pin "35") (pinfunction "35_35") (pintype "passive"))
      (node (ref "P4") (pin "5") (pinfunction "5_5") (pintype "passive"))
      (node (ref "P4") (pin "7") (pinfunction "7_7") (pintype "passive"))
      (node (ref "P4") (pin "9") (pinfunction "9_9") (pintype "passive"))
      (node (ref "P5") (pin "1") (pinfunction "1_1") (pintype "passive"))
      (node (ref "P5") (pin "11") (pinfunction "11_11") (pintype "passive"))
      (node (ref "P5") (pin "3") (pinfunction "3_3") (pintype "passive"))
      (node (ref "P5") (pin "5") (pinfunction "5_5") (pintype "passive"))
      (node (ref "P5") (pin "7") (pinfunction "7_7") (pintype "passive"))
      (node (ref "P5") (pin "9") (pinfunction "9_9") (pintype "passive"))
      (node (ref "R13") (pin "2") (pinfunction "2_2") (pintype "passive"))
      (node (ref "U1") (pin "20") (pinfunction "VCC_20") (pintype "passive"))
      (node (ref "U3") (pin "20") (pinfunction "VCC_20") (pintype "passive"))
      (node (ref "U4") (pin "20") (pinfunction "VCC_20") (pintype "passive"))
    )
    (net (code "52") (name "AGND") (class "Default")
      (node (ref "C18") (pin "1") (pinfunction "1_1") (pintype "passive"))
      (node (ref "C19") (pin "1") (pinfunction "1_1") (pintype "passive"))
      (node (ref "R33") (pin "1") (pinfunction "1_1") (pintype "passive"))
      (node (ref "U5") (pin "30") (pinfunction "VSSA_30") (pintype "passive"))
      (node (ref "U5") (pin "31") (pinfunction "VREF-_31") (pintype "passive"))
    )
    (net (code "53") (name "GND") (class "Default")
      (node (ref "C1") (pin "N") (pintype "passive"))
      (node (ref "C10") (pin "1") (pinfunction "1_1") (pintype "passive"))
      (node (ref "C11") (pin "2") (pinfunction "2_2") (pintype "passive"))
      (node (ref "C12") (pin "2") (pinfunction "2_2") (pintype "passive"))
      (node (ref "C13") (pin "1") (pinfunction "1_1") (pintype "passive"))
      (node (ref "C14") (pin "1") (pinfunction "1_1") (pintype "passive"))
      (node (ref "C15") (pin "1") (pinfunction "1_1") (pintype "passive"))
      (node (ref "C16") (pin "1") (pinfunction "1_1") (pintype "passive"))
      (node (ref "C17") (pin "1") (pinfunction "1_1") (pintype "passive"))
      (node (ref "C2") (pin "N") (pintype "passive"))
      (node (ref "C20") (pin "1") (pinfunction "1_1") (pintype "passive"))
      (node (ref "C21") (pin "1") (pinfunction "1_1") (pintype "passive"))
      (node (ref "C22") (pin "1") (pinfunction "1_1") (pintype "passive"))
      (node (ref "C23") (pin "1") (pinfunction "1_1") (pintype "passive"))
      (node (ref "C24") (pin "1") (pinfunction "1_1") (pintype "passive"))
      (node (ref "C25") (pin "1") (pinfunction "1_1") (pintype "passive"))
      (node (ref "C26") (pin "1") (pinfunction "1_1") (pintype "passive"))
      (node (ref "C27") (pin "1") (pinfunction "1_1") (pintype "passive"))
      (node (ref "C28") (pin "1") (pinfunction "1_1") (pintype "passive"))
      (node (ref "C29") (pin "1") (pinfunction "1_1") (pintype "passive"))
      (node (ref "C3") (pin "1") (pinfunction "1_1") (pintype "passive"))
      (node (ref "C30") (pin "1") (pinfunction "1_1") (pintype "passive"))
      (node (ref "C31") (pin "2") (pinfunction "2_2") (pintype "passive"))
      (node (ref "C32") (pin "2") (pinfunction "2_2") (pintype "passive"))
      (node (ref "C33") (pin "2") (pinfunction "2_2") (pintype "passive"))
      (node (ref "C34") (pin "2") (pinfunction "2_2") (pintype "passive"))
      (node (ref "C35") (pin "2") (pinfunction "2_2") (pintype "passive"))
      (node (ref "C36") (pin "2") (pinfunction "2_2") (pintype "passive"))
      (node (ref "C37") (pin "2") (pinfunction "2_2") (pintype "passive"))
      (node (ref "C38") (pin "2") (pinfunction "2_2") (pintype "passive"))
      (node (ref "C39") (pin "2") (pinfunction "2_2") (pintype "passive"))
      (node (ref "C4") (pin "N") (pintype "passive"))
      (node (ref "C40") (pin "2") (pinfunction "2_2") (pintype "passive"))
      (node (ref "C41") (pin "2") (pinfunction "2_2") (pintype "passive"))
      (node (ref "C42") (pin "2") (pinfunction "2_2") (pintype "passive"))
      (node (ref "C5") (pin "N") (pintype "passive"))
      (node (ref "C6") (pin "1") (pinfunction "1_1") (pintype "passive"))
      (node (ref "C9") (pin "2") (pinfunction "2_2") (pintype "passive"))
      (node (ref "D3") (pin "A") (pinfunction "A_A") (pintype "passive"))
      (node (ref "J1") (pin "1") (pinfunction "GND_1") (pintype "passive"))
      (node (ref "J1") (pin "13") (pinfunction "GND_13") (pintype "passive"))
      (node (ref "P2") (pin "1") (pinfunction "1_1") (pintype "passive"))
      (node (ref "P4") (pin "10") (pinfunction "10_10") (pintype "passive"))
      (node (ref "P4") (pin "12") (pinfunction "12_12") (pintype "passive"))
      (node (ref "P4") (pin "14") (pinfunction "14_14") (pintype "passive"))
      (node (ref "P4") (pin "16") (pinfunction "16_16") (pintype "passive"))
      (node (ref "P4") (pin "18") (pinfunction "18_18") (pintype "passive"))
      (node (ref "P4") (pin "2") (pinfunction "2_2") (pintype "passive"))
      (node (ref "P4") (pin "20") (pinfunction "20_20") (pintype "passive"))
      (node (ref "P4") (pin "22") (pinfunction "22_22") (pintype "passive"))
      (node (ref "P4") (pin "24") (pinfunction "24_24") (pintype "passive"))
      (node (ref "P4") (pin "26") (pinfunction "26_26") (pintype "passive"))
      (node (ref "P4") (pin "28") (pinfunction "28_28") (pintype "passive"))
      (node (ref "P4") (pin "30") (pinfunction "30_30") (pintype "passive"))
      (node (ref "P4") (pin "32") (pinfunction "32_32") (pintype "passive"))
      (node (ref "P4") (pin "34") (pinfunction "34_34") (pintype "passive"))
      (node (ref "P4") (pin "36") (pinfunction "36_36") (pintype "passive"))
      (node (ref "P4") (pin "4") (pinfunction "4_4") (pintype "passive"))
      (node (ref "P4") (pin "6") (pinfunction "6_6") (pintype "passive"))
      (node (ref "P4") (pin "8") (pinfunction "8_8") (pintype "passive"))
      (node (ref "P5") (pin "10") (pinfunction "10_10") (pintype "passive"))
      (node (ref "P5") (pin "12") (pinfunction "12_12") (pintype "passive"))
      (node (ref "P5") (pin "2") (pinfunction "2_2") (pintype "passive"))
      (node (ref "P5") (pin "4") (pinfunction "4_4") (pintype "passive"))
      (node (ref "P5") (pin "6") (pinfunction "6_6") (pintype "passive"))
      (node (ref "P5") (pin "8") (pinfunction "8_8") (pintype "passive"))
      (node (ref "P6") (pin "3") (pinfunction "3_3") (pintype "passive"))
      (node (ref "R11") (pin "1") (pinfunction "1_1") (pintype "passive"))
      (node (ref "R14") (pin "1") (pinfunction "1_1") (pintype "passive"))
      (node (ref "R33") (pin "2") (pinfunction "2_2") (pintype "passive"))
      (node (ref "R34") (pin "2") (pinfunction "2_2") (pintype "passive"))
      (node (ref "U1") (pin "10") (pinfunction "GND_10") (pintype "passive"))
      (node (ref "U2") (pin "2") (pinfunction "ISWE_2") (pintype "output"))
      (node (ref "U2") (pin "4") (pinfunction "GND_4") (pintype "passive"))
      (node (ref "U3") (pin "10") (pinfunction "GND_10") (pintype "passive"))
      (node (ref "U4") (pin "10") (pinfunction "GND_10") (pintype "passive"))
      (node (ref "U5") (pin "107") (pinfunction "VSS_2_107") (pintype "passive"))
      (node (ref "U5") (pin "120") (pinfunction "VSS_10_120") (pintype "passive"))
      (node (ref "U5") (pin "130") (pinfunction "VSS_11_130") (pintype "passive"))
      (node (ref "U5") (pin "143") (pinfunction "VSS_3_143") (pintype "passive"))
      (node (ref "U5") (pin "16") (pinfunction "VSS_5_16") (pintype "passive"))
      (node (ref "U5") (pin "38") (pinfunction "VSS_4_38") (pintype "passive"))
      (node (ref "U5") (pin "48") (pinfunction "PB2/BOOT1_48") (pintype "passive"))
      (node (ref "U5") (pin "51") (pinfunction "VSS_6_51") (pintype "passive"))
      (node (ref "U5") (pin "61") (pinfunction "VSS_7_61") (pintype "passive"))
      (node (ref "U5") (pin "71") (pinfunction "VSS_1_71") (pintype "passive"))
      (node (ref "U5") (pin "83") (pinfunction "VSS_8_83") (pintype "passive"))
      (node (ref "U5") (pin "94") (pinfunction "VSS_9_94") (pintype "passive"))
      (node (ref "U6") (pin "1") (pinfunction "GND_1") (pintype "passive"))
      (node (ref "Y1") (pin "2") (pinfunction "2_2") (pintype "passive"))
      (node (ref "Y1") (pin "3") (pinfunction "3_3") (pintype "passive"))
    )
    (net (code "54") (name "Net-(C7-Pad1)") (class "Default")
      (node (ref "C7") (pin "1") (pinfunction "1_1") (pintype "passive"))
      (node (ref "R3") (pin "2") (pinfunction "2_2") (pintype "passive"))
    )
    (net (code "55") (name "Net-(C15-Pad2)") (class "Default")
      (node (ref "C15") (pin "2") (pinfunction "2_2") (pintype "passive"))
      (node (ref "R31") (pin "2") (pinfunction "2_2") (pintype "passive"))
      (node (ref "Y1") (pin "1") (pinfunction "1_1") (pintype "passive"))
    )
    (net (code "56") (name "Net-(C17-Pad2)") (class "Default")
      (node (ref "C17") (pin "2") (pinfunction "2_2") (pintype "passive"))
      (node (ref "R32") (pin "2") (pinfunction "2_2") (pintype "passive"))
      (node (ref "Y2") (pin "1") (pinfunction "1_1") (pintype "passive"))
    )
    (net (code "57") (name "Net-(D1-PadA)") (class "Default")
      (node (ref "D1") (pin "A") (pinfunction "A_A") (pintype "passive"))
      (node (ref "Q1") (pin "B") (pinfunction "B_B") (pintype "passive"))
      (node (ref "Q2") (pin "B") (pinfunction "B_B") (pintype "passive"))
      (node (ref "R1") (pin "1") (pinfunction "1_1") (pintype "passive"))
      (node (ref "R12") (pin "2") (pinfunction "2_2") (pintype "passive"))
    )
    (net (code "58") (name "Net-(D2-PadA)") (class "Default")
      (node (ref "D2") (pin "A") (pinfunction "A_A") (pintype "passive"))
      (node (ref "Q1") (pin "E") (pinfunction "E_E") (pintype "passive"))
      (node (ref "Q2") (pin "C") (pinfunction "C_C") (pintype "passive"))
      (node (ref "T1") (pin "G") (pinfunction "G_G") (pintype "passive"))
    )
    (net (code "59") (name "Net-(D3-PadK)") (class "Default")
      (node (ref "D3") (pin "K") (pinfunction "K_K") (pintype "passive"))
      (node (ref "L1") (pin "1") (pinfunction "1_1") (pintype "passive"))
      (node (ref "R3") (pin "1") (pinfunction "1_1") (pintype "passive"))
      (node (ref "T1") (pin "D") (pinfunction "D_D") (pintype "passive"))
    )
    (net (code "60") (name "Net-(D4-PadA)") (class "Default")
      (node (ref "D4") (pin "A") (pinfunction "A_A") (pintype "passive"))
      (node (ref "Q2") (pin "E") (pinfunction "E_E") (pintype "passive"))
      (node (ref "R11") (pin "2") (pinfunction "2_2") (pintype "passive"))
    )
    (net (code "61") (name "Net-(P1-Pad1)") (class "Default")
      (node (ref "P1") (pin "1") (pinfunction "1_1") (pintype "passive"))
      (node (ref "R2") (pin "2") (pinfunction "2_2") (pintype "passive"))
    )
    (net (code "62") (name "Net-(P1-Pad2)") (class "Default")
      (node (ref "P1") (pin "2") (pinfunction "2_2") (pintype "passive"))
      (node (ref "R4") (pin "2") (pinfunction "2_2") (pintype "passive"))
    )
    (net (code "63") (name "Net-(P1-Pad3)") (class "Default")
      (node (ref "P1") (pin "3") (pinfunction "3_3") (pintype "passive"))
      (node (ref "R5") (pin "2") (pinfunction "2_2") (pintype "passive"))
    )
    (net (code "64") (name "Net-(P1-Pad4)") (class "Default")
      (node (ref "P1") (pin "4") (pinfunction "4_4") (pintype "passive"))
      (node (ref "R6") (pin "2") (pinfunction "2_2") (pintype "passive"))
    )
    (net (code "65") (name "Net-(P1-Pad5)") (class "Default")
      (node (ref "P1") (pin "5") (pinfunction "5_5") (pintype "passive"))
      (node (ref "R7") (pin "2") (pinfunction "2_2") (pintype "passive"))
    )
    (net (code "66") (name "Net-(P1-Pad6)") (class "Default")
      (node (ref "P1") (pin "6") (pinfunction "6_6") (pintype "passive"))
      (node (ref "R8") (pin "2") (pinfunction "2_2") (pintype "passive"))
    )
    (net (code "67") (name "Net-(P1-Pad7)") (class "Default")
      (node (ref "P1") (pin "7") (pinfunction "7_7") (pintype "passive"))
      (node (ref "R9") (pin "2") (pinfunction "2_2") (pintype "passive"))
    )
    (net (code "68") (name "Net-(P1-Pad8)") (class "Default")
      (node (ref "P1") (pin "8") (pinfunction "8_8") (pintype "passive"))
      (node (ref "R10") (pin "2") (pinfunction "2_2") (pintype "passive"))
    )
    (net (code "69") (name "Net-(P1-Pad9)") (class "Default")
      (node (ref "P1") (pin "9") (pinfunction "9_9") (pintype "passive"))
      (node (ref "R15") (pin "2") (pinfunction "2_2") (pintype "passive"))
    )
    (net (code "70") (name "Net-(P1-Pad10)") (class "Default")
      (node (ref "P1") (pin "10") (pinfunction "10_10") (pintype "passive"))
      (node (ref "R16") (pin "2") (pinfunction "2_2") (pintype "passive"))
    )
    (net (code "71") (name "Net-(P1-Pad11)") (class "Default")
      (node (ref "P1") (pin "11") (pinfunction "11_11") (pintype "passive"))
      (node (ref "R17") (pin "2") (pinfunction "2_2") (pintype "passive"))
    )
    (net (code "72") (name "Net-(P1-Pad12)") (class "Default")
      (node (ref "P1") (pin "12") (pinfunction "12_12") (pintype "passive"))
      (node (ref "R18") (pin "2") (pinfunction "2_2") (pintype "passive"))
    )
    (net (code "73") (name "Net-(P1-Pad13)") (class "Default")
      (node (ref "P1") (pin "13") (pinfunction "13_13") (pintype "passive"))
      (node (ref "R19") (pin "2") (pinfunction "2_2") (pintype "passive"))
    )
    (net (code "74") (name "Net-(P1-Pad14)") (class "Default")
      (node (ref "P1") (pin "14") (pinfunction "14_14") (pintype "passive"))
      (node (ref "R20") (pin "2") (pinfunction "2_2") (pintype "passive"))
    )
    (net (code "75") (name "Net-(P1-Pad15)") (class "Default")
      (node (ref "P1") (pin "15") (pinfunction "15_15") (pintype "passive"))
      (node (ref "R21") (pin "2") (pinfunction "2_2") (pintype "passive"))
    )
    (net (code "76") (name "Net-(P1-Pad16)") (class "Default")
      (node (ref "P1") (pin "16") (pinfunction "16_16") (pintype "passive"))
      (node (ref "R22") (pin "2") (pinfunction "2_2") (pintype "passive"))
    )
    (net (code "77") (name "Net-(P1-Pad17)") (class "Default")
      (node (ref "P1") (pin "17") (pinfunction "17_17") (pintype "passive"))
      (node (ref "R23") (pin "2") (pinfunction "2_2") (pintype "passive"))
    )
    (net (code "78") (name "Net-(P1-Pad18)") (class "Default")
      (node (ref "P1") (pin "18") (pinfunction "18_18") (pintype "passive"))
      (node (ref "R24") (pin "2") (pinfunction "2_2") (pintype "passive"))
    )
    (net (code "79") (name "Net-(P3-Pad1)") (class "Default")
      (node (ref "P3") (pin "1") (pinfunction "1_1") (pintype "passive"))
      (node (ref "R25") (pin "2") (pinfunction "2_2") (pintype "passive"))
    )
    (net (code "80") (name "Net-(P3-Pad2)") (class "Default")
      (node (ref "P3") (pin "2") (pinfunction "2_2") (pintype "passive"))
      (node (ref "R26") (pin "2") (pinfunction "2_2") (pintype "passive"))
    )
    (net (code "81") (name "Net-(P3-Pad3)") (class "Default")
      (node (ref "P3") (pin "3") (pinfunction "3_3") (pintype "passive"))
      (node (ref "R27") (pin "2") (pinfunction "2_2") (pintype "passive"))
    )
    (net (code "82") (name "Net-(P3-Pad4)") (class "Default")
      (node (ref "P3") (pin "4") (pinfunction "4_4") (pintype "passive"))
      (node (ref "R28") (pin "2") (pinfunction "2_2") (pintype "passive"))
    )
    (net (code "83") (name "Net-(P3-Pad5)") (class "Default")
      (node (ref "P3") (pin "5") (pinfunction "5_5") (pintype "passive"))
      (node (ref "R29") (pin "2") (pinfunction "2_2") (pintype "passive"))
    )
    (net (code "84") (name "Net-(P3-Pad6)") (class "Default")
      (node (ref "P3") (pin "6") (pinfunction "6_6") (pintype "passive"))
      (node (ref "R30") (pin "2") (pinfunction "2_2") (pintype "passive"))
    )
    (net (code "85") (name "Net-(U1-1Y0)") (class "Default")
      (node (ref "R2") (pin "1") (pinfunction "1_1") (pintype "passive"))
      (node (ref "U1") (pin "18") (pinfunction "1Y0_18") (pintype "passive"))
    )
    (net (code "86") (name "Net-(U1-1Y1)") (class "Default")
      (node (ref "R5") (pin "1") (pinfunction "1_1") (pintype "passive"))
      (node (ref "U1") (pin "16") (pinfunction "1Y1_16") (pintype "passive"))
    )
    (net (code "87") (name "Net-(U1-1Y2)") (class "Default")
      (node (ref "R7") (pin "1") (pinfunction "1_1") (pintype "passive"))
      (node (ref "U1") (pin "14") (pinfunction "1Y2_14") (pintype "passive"))
    )
    (net (code "88") (name "Net-(U1-1Y3)") (class "Default")
      (node (ref "R9") (pin "1") (pinfunction "1_1") (pintype "passive"))
      (node (ref "U1") (pin "12") (pinfunction "1Y3_12") (pintype "passive"))
    )
    (net (code "89") (name "Net-(U1-2A0)") (class "Default")
      (node (ref "R4") (pin "1") (pinfunction "1_1") (pintype "passive"))
      (node (ref "U1") (pin "17") (pinfunction "2A0_17") (pintype "passive"))
    )
    (net (code "90") (name "Net-(U1-2A1)") (class "Default")
      (node (ref "R6") (pin "1") (pinfunction "1_1") (pintype "passive"))
      (node (ref "U1") (pin "15") (pinfunction "2A1_15") (pintype "passive"))
    )
    (net (code "91") (name "Net-(U1-2A2)") (class "Default")
      (node (ref "R8") (pin "1") (pinfunction "1_1") (pintype "passive"))
      (node (ref "U1") (pin "13") (pinfunction "2A2_13") (pintype "passive"))
    )
    (net (code "92") (name "Net-(U1-2A3)") (class "Default")
      (node (ref "R10") (pin "1") (pinfunction "1_1") (pintype "passive"))
      (node (ref "U1") (pin "11") (pinfunction "2A3_11") (pintype "passive"))
    )
    (net (code "93") (name "Net-(U2-COMP)") (class "Default")
      (node (ref "C8") (pin "1") (pinfunction "1_1") (pintype "passive"))
      (node (ref "R13") (pin "1") (pinfunction "1_1") (pintype "passive"))
      (node (ref "R14") (pin "2") (pinfunction "2_2") (pintype "passive"))
      (node (ref "U2") (pin "5") (pinfunction "COMP_5") (pintype "input"))
    )
    (net (code "94") (name "Net-(U2-IDC)") (class "Default")
      (node (ref "R12") (pin "1") (pinfunction "1_1") (pintype "passive"))
      (node (ref "U2") (pin "1") (pinfunction "ISWC_1") (pintype "output"))
      (node (ref "U2") (pin "8") (pinfunction "IDC_8") (pintype "passive"))
    )
    (net (code "95") (name "Net-(U2-TCAP)") (class "Default")
      (node (ref "C7") (pin "2") (pinfunction "2_2") (pintype "passive"))
      (node (ref "C9") (pin "1") (pinfunction "1_1") (pintype "passive"))
      (node (ref "U2") (pin "3") (pinfunction "TCAP_3") (pintype "passive"))
    )
    (net (code "96") (name "Net-(U3-1Y0)") (class "Default")
      (node (ref "R15") (pin "1") (pinfunction "1_1") (pintype "passive"))
      (node (ref "U3") (pin "18") (pinfunction "1Y0_18") (pintype "passive"))
    )
    (net (code "97") (name "Net-(U3-1Y1)") (class "Default")
      (node (ref "R17") (pin "1") (pinfunction "1_1") (pintype "passive"))
      (node (ref "U3") (pin "16") (pinfunction "1Y1_16") (pintype "passive"))
    )
    (net (code "98") (name "Net-(U3-1Y2)") (class "Default")
      (node (ref "R19") (pin "1") (pinfunction "1_1") (pintype "passive"))
      (node (ref "U3") (pin "14") (pinfunction "1Y2_14") (pintype "passive"))
    )
    (net (code "99") (name "Net-(U3-1Y3)") (class "Default")
      (node (ref "R21") (pin "1") (pinfunction "1_1") (pintype "passive"))
      (node (ref "U3") (pin "12") (pinfunction "1Y3_12") (pintype "passive"))
    )
    (net (code "100") (name "Net-(U3-2A0)") (class "Default")
      (node (ref "R16") (pin "1") (pinfunction "1_1") (pintype "passive"))
      (node (ref "U3") (pin "17") (pinfunction "2A0_17") (pintype "passive"))
    )
    (net (code "101") (name "Net-(U3-2A1)") (class "Default")
      (node (ref "R18") (pin "1") (pinfunction "1_1") (pintype "passive"))
      (node (ref "U3") (pin "15") (pinfunction "2A1_15") (pintype "passive"))
    )
    (net (code "102") (name "Net-(U3-2A2)") (class "Default")
      (node (ref "R20") (pin "1") (pinfunction "1_1") (pintype "passive"))
      (node (ref "U3") (pin "13") (pinfunction "2A2_13") (pintype "passive"))
    )
    (net (code "103") (name "Net-(U3-2A3)") (class "Default")
      (node (ref "R22") (pin "1") (pinfunction "1_1") (pintype "passive"))
      (node (ref "U3") (pin "11") (pinfunction "2A3_11") (pintype "passive"))
    )
    (net (code "104") (name "Net-(U4-1Y0)") (class "Default")
      (node (ref "R23") (pin "1") (pinfunction "1_1") (pintype "passive"))
      (node (ref "U4") (pin "18") (pinfunction "1Y0_18") (pintype "passive"))
    )
    (net (code "105") (name "Net-(U4-1Y1)") (class "Default")
      (node (ref "R25") (pin "1") (pinfunction "1_1") (pintype "passive"))
      (node (ref "U4") (pin "16") (pinfunction "1Y1_16") (pintype "passive"))
    )
    (net (code "106") (name "Net-(U4-1Y2)") (class "Default")
      (node (ref "R27") (pin "1") (pinfunction "1_1") (pintype "passive"))
      (node (ref "U4") (pin "14") (pinfunction "1Y2_14") (pintype "passive"))
    )
    (net (code "107") (name "Net-(U4-1Y3)") (class "Default")
      (node (ref "R29") (pin "1") (pinfunction "1_1") (pintype "passive"))
      (node (ref "U4") (pin "12") (pinfunction "1Y3_12") (pintype "passive"))
    )
    (net (code "108") (name "Net-(U4-2A0)") (class "Default")
      (node (ref "R24") (pin "1") (pinfunction "1_1") (pintype "passive"))
      (node (ref "U4") (pin "17") (pinfunction "2A0_17") (pintype "passive"))
    )
    (net (code "109") (name "Net-(U4-2A1)") (class "Default")
      (node (ref "R26") (pin "1") (pinfunction "1_1") (pintype "passive"))
      (node (ref "U4") (pin "15") (pinfunction "2A1_15") (pintype "passive"))
    )
    (net (code "110") (name "Net-(U4-2A2)") (class "Default")
      (node (ref "R28") (pin "1") (pinfunction "1_1") (pintype "passive"))
      (node (ref "U4") (pin "13") (pinfunction "2A2_13") (pintype "passive"))
    )
    (net (code "111") (name "Net-(U4-2A3)") (class "Default")
      (node (ref "R30") (pin "1") (pinfunction "1_1") (pintype "passive"))
      (node (ref "U4") (pin "11") (pinfunction "2A3_11") (pintype "passive"))
    )
    (net (code "112") (name "VCC") (class "Default")
      (node (ref "C20") (pin "2") (pinfunction "2_2") (pintype "passive"))
      (node (ref "C21") (pin "2") (pinfunction "2_2") (pintype "passive"))
      (node (ref "C22") (pin "2") (pinfunction "2_2") (pintype "passive"))
      (node (ref "C23") (pin "2") (pinfunction "2_2") (pintype "passive"))
      (node (ref "C24") (pin "2") (pinfunction "2_2") (pintype "passive"))
      (node (ref "C25") (pin "2") (pinfunction "2_2") (pintype "passive"))
      (node (ref "C26") (pin "2") (pinfunction "2_2") (pintype "passive"))
      (node (ref "C27") (pin "2") (pinfunction "2_2") (pintype "passive"))
      (node (ref "C28") (pin "2") (pinfunction "2_2") (pintype "passive"))
      (node (ref "C29") (pin "2") (pinfunction "2_2") (pintype "passive"))
      (node (ref "C30") (pin "2") (pinfunction "2_2") (pintype "passive"))
      (node (ref "C31") (pin "1") (pinfunction "1_1") (pintype "passive"))
      (node (ref "C32") (pin "1") (pinfunction "1_1") (pintype "passive"))
      (node (ref "C33") (pin "1") (pinfunction "1_1") (pintype "passive"))
      (node (ref "C34") (pin "1") (pinfunction "1_1") (pintype "passive"))
      (node (ref "C35") (pin "1") (pinfunction "1_1") (pintype "passive"))
      (node (ref "C36") (pin "1") (pinfunction "1_1") (pintype "passive"))
      (node (ref "C37") (pin "1") (pinfunction "1_1") (pintype "passive"))
      (node (ref "C38") (pin "1") (pinfunction "1_1") (pintype "passive"))
      (node (ref "C39") (pin "1") (pinfunction "1_1") (pintype "passive"))
      (node (ref "C40") (pin "1") (pinfunction "1_1") (pintype "passive"))
      (node (ref "C41") (pin "1") (pinfunction "1_1") (pintype "passive"))
      (node (ref "L2") (pin "1") (pinfunction "1_1") (pintype "passive"))
      (node (ref "P6") (pin "1") (pinfunction "1_1") (pintype "passive"))
      (node (ref "U5") (pin "108") (pinfunction "VDD_2_108") (pintype "passive"))
      (node (ref "U5") (pin "121") (pinfunction "VCC_10_121") (pintype "passive"))
      (node (ref "U5") (pin "131") (pinfunction "VDD_11_131") (pintype "passive"))
      (node (ref "U5") (pin "144") (pinfunction "VDD_3_144") (pintype "passive"))
      (node (ref "U5") (pin "17") (pinfunction "VDD_5_17") (pintype "passive"))
      (node (ref "U5") (pin "39") (pinfunction "VDD_4_39") (pintype "passive"))
      (node (ref "U5") (pin "52") (pinfunction "VDD_6_52") (pintype "passive"))
      (node (ref "U5") (pin "62") (pinfunction "VDD_7_62") (pintype "passive"))
      (node (ref "U5") (pin "72") (pinfunction "VDD_1_72") (pintype "passive"))
      (node (ref "U5") (pin "84") (pinfunction "VDD_8_84") (pintype "passive"))
      (node (ref "U5") (pin "95") (pinfunction "VDD_9_95") (pintype "passive"))
    )
    (net (code "113") (name "VDA") (class "Default")
      (node (ref "C18") (pin "2") (pinfunction "2_2") (pintype "passive"))
      (node (ref "C19") (pin "2") (pinfunction "2_2") (pintype "passive"))
      (node (ref "L2") (pin "2") (pinfunction "2_2") (pintype "passive"))
      (node (ref "U5") (pin "33") (pinfunction "VDDA_33") (pintype "passive"))
    )
    (net (code "114") (name "VDU_bat") (class "Default")
      (node (ref "U5") (pin "6") (pinfunction "VBAT_6") (pintype "passive"))
    )
    (net (code "115") (name "VIN") (class "Default")
      (node (ref "C1") (pin "P") (pintype "passive"))
      (node (ref "C10") (pin "2") (pinfunction "2_2") (pintype "passive"))
      (node (ref "C11") (pin "1") (pinfunction "1_1") (pintype "passive"))
      (node (ref "C2") (pin "P") (pintype "passive"))
      (node (ref "C3") (pin "2") (pinfunction "2_2") (pintype "passive"))
      (node (ref "D1") (pin "K") (pinfunction "K_K") (pintype "passive"))
      (node (ref "D2") (pin "K") (pinfunction "K_K") (pintype "passive"))
      (node (ref "D4") (pin "K") (pinfunction "K_K") (pintype "passive"))
      (node (ref "P2") (pin "2") (pinfunction "2_2") (pintype "passive"))
      (node (ref "Q1") (pin "C") (pinfunction "C_C") (pintype "passive"))
      (node (ref "R1") (pin "2") (pinfunction "2_2") (pintype "passive"))
      (node (ref "T1") (pin "S") (pinfunction "S_S") (pintype "passive"))
      (node (ref "U2") (pin "6") (pinfunction "VCC_6") (pintype "passive"))
      (node (ref "U2") (pin "7") (pinfunction "IPK_7") (pintype "passive"))
      (node (ref "U6") (pin "3") (pinfunction "VIN_3") (pintype "passive"))
    )
    (net (code "116") (name "VREFH") (class "Default")
      (node (ref "U5") (pin "32") (pinfunction "VREF+_32") (pintype "passive"))
    )
    (net (code "117") (name "unconnected-(J1-NC-Pad14)") (class "Default")
      (node (ref "J1") (pin "14") (pinfunction "NC_14") (pintype "passive+no_connect"))
    )
    (net (code "118") (name "unconnected-(J1-VCC_In-Pad2)") (class "Default")
      (node (ref "J1") (pin "2") (pinfunction "VCC_In_2") (pintype "passive"))
    )
    (net (code "119") (name "unconnected-(U1-~{1OE}-Pad1)") (class "Default")
      (node (ref "U1") (pin "1") (pinfunction "~{1OE}_1") (pintype "passive"))
    )
    (net (code "120") (name "unconnected-(U1-~{2OE}-Pad19)") (class "Default")
      (node (ref "U1") (pin "19") (pinfunction "~{2OE}_19") (pintype "passive"))
    )
    (net (code "121") (name "unconnected-(U3-~{1OE}-Pad1)") (class "Default")
      (node (ref "U3") (pin "1") (pinfunction "~{1OE}_1") (pintype "passive"))
    )
    (net (code "122") (name "unconnected-(U3-~{2OE}-Pad19)") (class "Default")
      (node (ref "U3") (pin "19") (pinfunction "~{2OE}_19") (pintype "passive"))
    )
    (net (code "123") (name "unconnected-(U4-~{1OE}-Pad1)") (class "Default")
      (node (ref "U4") (pin "1") (pinfunction "~{1OE}_1") (pintype "passive"))
    )
    (net (code "124") (name "unconnected-(U4-~{2OE}-Pad19)") (class "Default")
      (node (ref "U4") (pin "19") (pinfunction "~{2OE}_19") (pintype "passive"))
    )
    (net (code "125") (name "unconnected-(U5-NC-Pad106)") (class "Default")
      (node (ref "U5") (pin "106") (pinfunction "NC_106") (pintype "passive+no_connect"))
    )
    (net (code "126") (name "unconnected-(U5-PA08-Pad100)") (class "Default")
      (node (ref "U5") (pin "100") (pinfunction "PA08_100") (pintype "passive"))
    )
    (net (code "127") (name "unconnected-(U5-PA11-Pad103)") (class "Default")
      (node (ref "U5") (pin "103") (pinfunction "PA11_103") (pintype "passive"))
    )
    (net (code "128") (name "unconnected-(U5-PA12-Pad104)") (class "Default")
      (node (ref "U5") (pin "104") (pinfunction "PA12_104") (pintype "passive"))
    )
    (net (code "129") (name "unconnected-(U5-PB0-Pad46)") (class "Default")
      (node (ref "U5") (pin "46") (pinfunction "PB0_46") (pintype "passive"))
    )
    (net (code "130") (name "unconnected-(U5-PB1-Pad47)") (class "Default")
      (node (ref "U5") (pin "47") (pinfunction "PB1_47") (pintype "passive"))
    )
    (net (code "131") (name "unconnected-(U5-PB5-Pad135)") (class "Default")
      (node (ref "U5") (pin "135") (pinfunction "PB5_135") (pintype "passive"))
    )
    (net (code "132") (name "unconnected-(U5-PB12-Pad73)") (class "Default")
      (node (ref "U5") (pin "73") (pinfunction "PB12_73") (pintype "passive"))
    )
    (net (code "133") (name "unconnected-(U5-PB13-Pad74)") (class "Default")
      (node (ref "U5") (pin "74") (pinfunction "PB13_74") (pintype "passive"))
    )
    (net (code "134") (name "unconnected-(U5-PB14-Pad75)") (class "Default")
      (node (ref "U5") (pin "75") (pinfunction "PB14_75") (pintype "passive"))
    )
    (net (code "135") (name "unconnected-(U5-PB15-Pad76)") (class "Default")
      (node (ref "U5") (pin "76") (pinfunction "PB15_76") (pintype "passive"))
    )
    (net (code "136") (name "unconnected-(U5-PC4-Pad44)") (class "Default")
      (node (ref "U5") (pin "44") (pinfunction "PC4_44") (pintype "passive"))
    )
    (net (code "137") (name "unconnected-(U5-PC5-Pad45)") (class "Default")
      (node (ref "U5") (pin "45") (pinfunction "PC5_45") (pintype "passive"))
    )
    (net (code "138") (name "unconnected-(U5-PC10-Pad111)") (class "Default")
      (node (ref "U5") (pin "111") (pinfunction "PC10_111") (pintype "passive"))
    )
    (net (code "139") (name "unconnected-(U5-PC11-Pad112)") (class "Default")
      (node (ref "U5") (pin "112") (pinfunction "PC11_112") (pintype "passive"))
    )
    (net (code "140") (name "unconnected-(U5-PC12-Pad113)") (class "Default")
      (node (ref "U5") (pin "113") (pinfunction "PC12_113") (pintype "passive"))
    )
    (net (code "141") (name "unconnected-(U5-PC13-TAMPER-RTC-Pad7)") (class "Default")
      (node (ref "U5") (pin "7") (pinfunction "PC13-TAMPER-RTC_7") (pintype "passive"))
    )
    (net (code "142") (name "unconnected-(U5-PD0-Pad114)") (class "Default")
      (node (ref "U5") (pin "114") (pinfunction "PD0_114") (pintype "passive"))
    )
    (net (code "143") (name "unconnected-(U5-PD1-Pad115)") (class "Default")
      (node (ref "U5") (pin "115") (pinfunction "PD1_115") (pintype "passive"))
    )
    (net (code "144") (name "unconnected-(U5-PD2-Pad116)") (class "Default")
      (node (ref "U5") (pin "116") (pinfunction "PD2_116") (pintype "passive"))
    )
    (net (code "145") (name "unconnected-(U5-PD3-Pad117)") (class "Default")
      (node (ref "U5") (pin "117") (pinfunction "PD3_117") (pintype "passive"))
    )
    (net (code "146") (name "unconnected-(U5-PD4-Pad118)") (class "Default")
      (node (ref "U5") (pin "118") (pinfunction "PD4_118") (pintype "passive"))
    )
    (net (code "147") (name "unconnected-(U5-PD7-Pad123)") (class "Default")
      (node (ref "U5") (pin "123") (pinfunction "PD7_123") (pintype "passive"))
    )
    (net (code "148") (name "unconnected-(U5-PD08-Pad77)") (class "Default")
      (node (ref "U5") (pin "77") (pinfunction "PD08_77") (pintype "passive"))
    )
    (net (code "149") (name "unconnected-(U5-PD09-Pad78)") (class "Default")
      (node (ref "U5") (pin "78") (pinfunction "PD09_78") (pintype "passive"))
    )
    (net (code "150") (name "unconnected-(U5-PD10-Pad79)") (class "Default")
      (node (ref "U5") (pin "79") (pinfunction "PD10_79") (pintype "passive"))
    )
    (net (code "151") (name "unconnected-(U5-PD11-Pad80)") (class "Default")
      (node (ref "U5") (pin "80") (pinfunction "PD11_80") (pintype "passive"))
    )
    (net (code "152") (name "unconnected-(U5-PD12-Pad81)") (class "Default")
      (node (ref "U5") (pin "81") (pinfunction "PD12_81") (pintype "passive"))
    )
    (net (code "153") (name "unconnected-(U5-PD13-Pad82)") (class "Default")
      (node (ref "U5") (pin "82") (pinfunction "PD13_82") (pintype "passive"))
    )
    (net (code "154") (name "unconnected-(U5-PD14-Pad85)") (class "Default")
      (node (ref "U5") (pin "85") (pinfunction "PD14_85") (pintype "passive"))
    )
    (net (code "155") (name "unconnected-(U5-PD15-Pad86)") (class "Default")
      (node (ref "U5") (pin "86") (pinfunction "PD15_86") (pintype "passive"))
    )
    (net (code "156") (name "unconnected-(U5-PE0-Pad141)") (class "Default")
      (node (ref "U5") (pin "141") (pinfunction "PE0_141") (pintype "passive"))
    )
    (net (code "157") (name "unconnected-(U5-PE1-Pad142)") (class "Default")
      (node (ref "U5") (pin "142") (pinfunction "PE1_142") (pintype "passive"))
    )
    (net (code "158") (name "unconnected-(U5-PE2-Pad1)") (class "Default")
      (node (ref "U5") (pin "1") (pinfunction "PE2_1") (pintype "passive"))
    )
    (net (code "159") (name "unconnected-(U5-PE3-Pad2)") (class "Default")
      (node (ref "U5") (pin "2") (pinfunction "PE3_2") (pintype "passive"))
    )
    (net (code "160") (name "unconnected-(U5-PE4-Pad3)") (class "Default")
      (node (ref "U5") (pin "3") (pinfunction "PE4_3") (pintype "passive"))
    )
    (net (code "161") (name "unconnected-(U5-PE7-Pad58)") (class "Default")
      (node (ref "U5") (pin "58") (pinfunction "PE7_58") (pintype "passive"))
    )
    (net (code "162") (name "unconnected-(U5-PE8-Pad59)") (class "Default")
      (node (ref "U5") (pin "59") (pinfunction "PE8_59") (pintype "passive"))
    )
    (net (code "163") (name "unconnected-(U5-PE9-Pad60)") (class "Default")
      (node (ref "U5") (pin "60") (pinfunction "PE9_60") (pintype "passive"))
    )
    (net (code "164") (name "unconnected-(U5-PE10-Pad63)") (class "Default")
      (node (ref "U5") (pin "63") (pinfunction "PE10_63") (pintype "passive"))
    )
    (net (code "165") (name "unconnected-(U5-PE11-Pad64)") (class "Default")
      (node (ref "U5") (pin "64") (pinfunction "PE11_64") (pintype "passive"))
    )
    (net (code "166") (name "unconnected-(U5-PE12-Pad65)") (class "Default")
      (node (ref "U5") (pin "65") (pinfunction "PE12_65") (pintype "passive"))
    )
    (net (code "167") (name "unconnected-(U5-PE13-Pad66)") (class "Default")
      (node (ref "U5") (pin "66") (pinfunction "PE13_66") (pintype "passive"))
    )
    (net (code "168") (name "unconnected-(U5-PE14-Pad67)") (class "Default")
      (node (ref "U5") (pin "67") (pinfunction "PE14_67") (pintype "passive"))
    )
    (net (code "169") (name "unconnected-(U5-PE15-Pad68)") (class "Default")
      (node (ref "U5") (pin "68") (pinfunction "PE15_68") (pintype "passive"))
    )
    (net (code "170") (name "unconnected-(U5-PF0-Pad10)") (class "Default")
      (node (ref "U5") (pin "10") (pinfunction "PF0_10") (pintype "passive"))
    )
    (net (code "171") (name "unconnected-(U5-PF1-Pad11)") (class "Default")
      (node (ref "U5") (pin "11") (pinfunction "PF1_11") (pintype "passive"))
    )
    (net (code "172") (name "unconnected-(U5-PF2-Pad12)") (class "Default")
      (node (ref "U5") (pin "12") (pinfunction "PF2_12") (pintype "passive"))
    )
    (net (code "173") (name "unconnected-(U5-PF3-Pad13)") (class "Default")
      (node (ref "U5") (pin "13") (pinfunction "PF3_13") (pintype "passive"))
    )
    (net (code "174") (name "unconnected-(U5-PF4-Pad14)") (class "Default")
      (node (ref "U5") (pin "14") (pinfunction "PF4_14") (pintype "passive"))
    )
    (net (code "175") (name "unconnected-(U5-PF5-Pad15)") (class "Default")
      (node (ref "U5") (pin "15") (pinfunction "PF5_15") (pintype "passive"))
    )
    (net (code "176") (name "unconnected-(U5-PF10-Pad22)") (class "Default")
      (node (ref "U5") (pin "22") (pinfunction "PF10_22") (pintype "passive"))
    )
    (net (code "177") (name "unconnected-(U5-PF11-Pad49)") (class "Default")
      (node (ref "U5") (pin "49") (pinfunction "PF11_49") (pintype "passive"))
    )
    (net (code "178") (name "unconnected-(U5-PF12-Pad50)") (class "Default")
      (node (ref "U5") (pin "50") (pinfunction "PF12_50") (pintype "passive"))
    )
    (net (code "179") (name "unconnected-(U5-PF13-Pad53)") (class "Default")
      (node (ref "U5") (pin "53") (pinfunction "PF13_53") (pintype "passive"))
    )
    (net (code "180") (name "unconnected-(U5-PF14-Pad54)") (class "Default")
      (node (ref "U5") (pin "54") (pinfunction "PF14_54") (pintype "passive"))
    )
    (net (code "181") (name "unconnected-(U5-PF15-Pad55)") (class "Default")
      (node (ref "U5") (pin "55") (pinfunction "PF15_55") (pintype "passive"))
    )
    (net (code "182") (name "unconnected-(U5-PG0-Pad56)") (class "Default")
      (node (ref "U5") (pin "56") (pinfunction "PG0_56") (pintype "passive"))
    )
    (net (code "183") (name "unconnected-(U5-PG1-Pad57)") (class "Default")
      (node (ref "U5") (pin "57") (pinfunction "PG1_57") (pintype "passive"))
    )
    (net (code "184") (name "unconnected-(U5-PG2-Pad87)") (class "Default")
      (node (ref "U5") (pin "87") (pinfunction "PG2_87") (pintype "passive"))
    )
    (net (code "185") (name "unconnected-(U5-PG3-Pad88)") (class "Default")
      (node (ref "U5") (pin "88") (pinfunction "PG3_88") (pintype "passive"))
    )
    (net (code "186") (name "unconnected-(U5-PG4-Pad89)") (class "Default")
      (node (ref "U5") (pin "89") (pinfunction "PG4_89") (pintype "passive"))
    )
    (net (code "187") (name "unconnected-(U5-PG5-Pad90)") (class "Default")
      (node (ref "U5") (pin "90") (pinfunction "PG5_90") (pintype "passive"))
    )
    (net (code "188") (name "unconnected-(U5-PG6-Pad91)") (class "Default")
      (node (ref "U5") (pin "91") (pinfunction "PG6_91") (pintype "passive"))
    )
    (net (code "189") (name "unconnected-(U5-PG7-Pad92)") (class "Default")
      (node (ref "U5") (pin "92") (pinfunction "PG7_92") (pintype "passive"))
    )
    (net (code "190") (name "unconnected-(U5-PG8-Pad93)") (class "Default")
      (node (ref "U5") (pin "93") (pinfunction "PG8_93") (pintype "passive"))
    )
    (net (code "191") (name "unconnected-(U5-PG09-Pad124)") (class "Default")
      (node (ref "U5") (pin "124") (pinfunction "PG09_124") (pintype "passive"))
    )
    (net (code "192") (name "unconnected-(U5-PG10-Pad125)") (class "Default")
      (node (ref "U5") (pin "125") (pinfunction "PG10_125") (pintype "passive"))
    )
    (net (code "193") (name "unconnected-(U5-PG11-Pad126)") (class "Default")
      (node (ref "U5") (pin "126") (pinfunction "PG11_126") (pintype "passive"))
    )
    (net (code "194") (name "unconnected-(U5-PG12-Pad127)") (class "Default")
      (node (ref "U5") (pin "127") (pinfunction "PG12_127") (pintype "passive"))
    )
    (net (code "195") (name "unconnected-(U5-PG13-Pad128)") (class "Default")
      (node (ref "U5") (pin "128") (pinfunction "PG13_128") (pintype "passive"))
    )
    (net (code "196") (name "unconnected-(U5-PG14-Pad129)") (class "Default")
      (node (ref "U5") (pin "129") (pinfunction "PG14_129") (pintype "passive"))
    )
    (net (code "197") (name "unconnected-(U5-PG15-Pad132)") (class "Default")
      (node (ref "U5") (pin "132") (pinfunction "PG15_132") (pintype "passive"))
    )
  )
)
